# AS3364_waveform_VCA_0402_DIL_w_two_separ.net
KiCad netlist of a schematic drawn in EAGLE
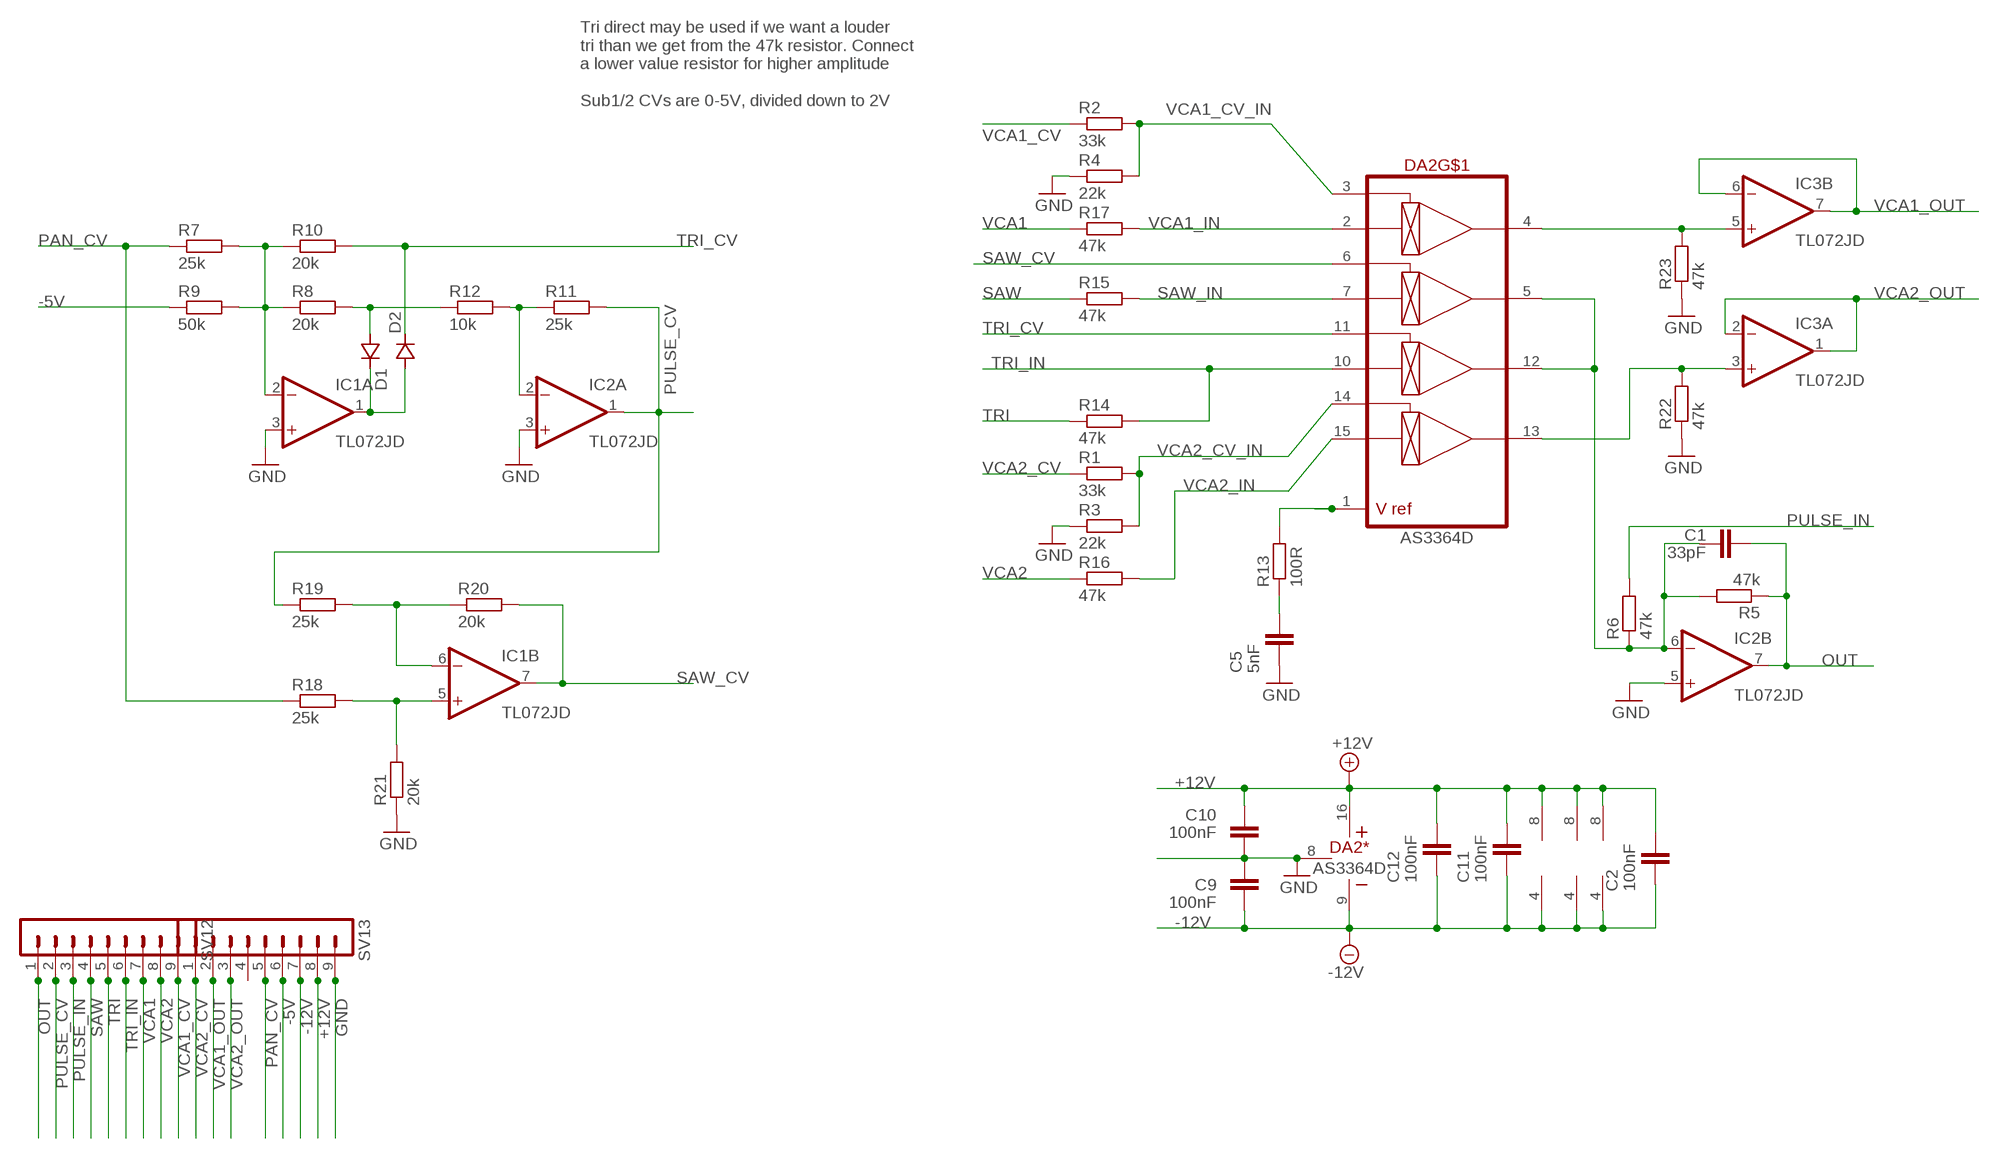
[diagram p0: schematic, sheet 1]

(export (version "E")
  (design (tool "Eeschema 10.0.6"))
  (components
    (comp (ref "C1")
      (value "33pF")
      (footprint "eagle-import:C0402")
      (libsource (lib "eagle-import") (part "C-EUC0402"))
    )
    (comp (ref "C2")
      (value "100nF")
      (footprint "eagle-import:C0402")
      (libsource (lib "eagle-import") (part "C-EUC0402"))
    )
    (comp (ref "C5")
      (value "5nF")
      (footprint "eagle-import:C0402")
      (libsource (lib "eagle-import") (part "C-EUC0402"))
    )
    (comp (ref "C9")
      (value "100nF")
      (footprint "eagle-import:C0402")
      (libsource (lib "eagle-import") (part "C-EUC0402"))
    )
    (comp (ref "C10")
      (value "100nF")
      (footprint "eagle-import:C0402")
      (libsource (lib "eagle-import") (part "C-EUC0402"))
    )
    (comp (ref "C11")
      (value "100nF")
      (footprint "eagle-import:C0402")
      (libsource (lib "eagle-import") (part "C-EUC0402"))
    )
    (comp (ref "C12")
      (value "100nF")
      (footprint "eagle-import:C0402")
      (libsource (lib "eagle-import") (part "C-EUC0402"))
    )
    (comp (ref "D1")
      (value "DIODESOD323")
      (footprint "eagle-import:SOD323J")
      (fields (field (name "MPN") "CDSOD323-T05C"))
      (libsource (lib "eagle-import") (part "DIODESOD323"))
    )
    (comp (ref "D2")
      (value "DIODESOD323")
      (footprint "eagle-import:SOD323J")
      (fields (field (name "MPN") "CDSOD323-T05C"))
      (libsource (lib "eagle-import") (part "DIODESOD323"))
    )
    (comp (ref "DA2")
      (value "AS3364D")
      (footprint "eagle-import:DIL16J")
      (libsource (lib "eagle-import") (part "AS3364D"))
    )
    (comp (ref "IC1")
      (value "TL072JD")
      (footprint "eagle-import:SO08J")
      (libsource (lib "eagle-import") (part "TL072JD"))
    )
    (comp (ref "IC2")
      (value "TL072JD")
      (footprint "eagle-import:SO08J")
      (libsource (lib "eagle-import") (part "TL072JD"))
    )
    (comp (ref "IC3")
      (value "TL072JD")
      (footprint "eagle-import:SO08J")
      (libsource (lib "eagle-import") (part "TL072JD"))
    )
    (comp (ref "R1")
      (value "33k")
      (footprint "eagle-import:R0402")
      (libsource (lib "eagle-import") (part "R-EU_R0402"))
    )
    (comp (ref "R2")
      (value "33k")
      (footprint "eagle-import:R0402")
      (libsource (lib "eagle-import") (part "R-EU_R0402"))
    )
    (comp (ref "R3")
      (value "22k")
      (footprint "eagle-import:R0402")
      (libsource (lib "eagle-import") (part "R-EU_R0402"))
    )
    (comp (ref "R4")
      (value "22k")
      (footprint "eagle-import:R0402")
      (libsource (lib "eagle-import") (part "R-EU_R0402"))
    )
    (comp (ref "R5")
      (value "47k")
      (footprint "eagle-import:R0402")
      (libsource (lib "eagle-import") (part "R-EU_R0402"))
    )
    (comp (ref "R6")
      (value "47k")
      (footprint "eagle-import:R0402")
      (libsource (lib "eagle-import") (part "R-EU_R0402"))
    )
    (comp (ref "R7")
      (value "25k")
      (footprint "eagle-import:R0402")
      (libsource (lib "eagle-import") (part "R-EU_R0402"))
    )
    (comp (ref "R8")
      (value "20k")
      (footprint "eagle-import:R0402")
      (libsource (lib "eagle-import") (part "R-EU_R0402"))
    )
    (comp (ref "R9")
      (value "50k")
      (footprint "eagle-import:R0402")
      (libsource (lib "eagle-import") (part "R-EU_R0402"))
    )
    (comp (ref "R10")
      (value "20k")
      (footprint "eagle-import:R0402")
      (libsource (lib "eagle-import") (part "R-EU_R0402"))
    )
    (comp (ref "R11")
      (value "25k")
      (footprint "eagle-import:R0402")
      (libsource (lib "eagle-import") (part "R-EU_R0402"))
    )
    (comp (ref "R12")
      (value "10k")
      (footprint "eagle-import:R0402")
      (libsource (lib "eagle-import") (part "R-EU_R0402"))
    )
    (comp (ref "R13")
      (value "100R")
      (footprint "eagle-import:R0402")
      (libsource (lib "eagle-import") (part "R-EU_R0402"))
    )
    (comp (ref "R14")
      (value "47k")
      (footprint "eagle-import:R0402")
      (libsource (lib "eagle-import") (part "R-EU_R0402"))
    )
    (comp (ref "R15")
      (value "47k")
      (footprint "eagle-import:R0402")
      (libsource (lib "eagle-import") (part "R-EU_R0402"))
    )
    (comp (ref "R16")
      (value "47k")
      (footprint "eagle-import:R0402")
      (libsource (lib "eagle-import") (part "R-EU_R0402"))
    )
    (comp (ref "R17")
      (value "47k")
      (footprint "eagle-import:R0402")
      (libsource (lib "eagle-import") (part "R-EU_R0402"))
    )
    (comp (ref "R18")
      (value "25k")
      (footprint "eagle-import:R0402")
      (libsource (lib "eagle-import") (part "R-EU_R0402"))
    )
    (comp (ref "R19")
      (value "25k")
      (footprint "eagle-import:R0402")
      (libsource (lib "eagle-import") (part "R-EU_R0402"))
    )
    (comp (ref "R20")
      (value "20k")
      (footprint "eagle-import:R0402")
      (libsource (lib "eagle-import") (part "R-EU_R0402"))
    )
    (comp (ref "R21")
      (value "20k")
      (footprint "eagle-import:R0402")
      (libsource (lib "eagle-import") (part "R-EU_R0402"))
    )
    (comp (ref "R22")
      (value "47k")
      (footprint "eagle-import:R0402")
      (libsource (lib "eagle-import") (part "R-EU_R0402"))
    )
    (comp (ref "R23")
      (value "47k")
      (footprint "eagle-import:R0402")
      (libsource (lib "eagle-import") (part "R-EU_R0402"))
    )
    (comp (ref "SV12")
      (value "MA09-1JP")
      (footprint "eagle-import:SIP-PIN09-1J")
      (libsource (lib "eagle-import") (part "MA09-1JP"))
    )
    (comp (ref "SV13")
      (value "MA09-1JP")
      (footprint "eagle-import:SIP-PIN09-1J")
      (libsource (lib "eagle-import") (part "MA09-1JP"))
    )
  )
  (nets
    (net (code "1") (name "+12V") (class "Default")
      (node (ref "C10") (pin "2") (pinfunction "2_2") (pintype "passive"))
      (node (ref "C11") (pin "2") (pinfunction "2_2") (pintype "passive"))
      (node (ref "C12") (pin "2") (pinfunction "2_2") (pintype "passive"))
      (node (ref "C2") (pin "2") (pinfunction "2_2") (pintype "passive"))
      (node (ref "DA2") (pin "16") (pinfunction "V+_16") (pintype "power_in"))
      (node (ref "IC1") (pin "8") (pinfunction "V+_8") (pintype "power_in"))
      (node (ref "IC2") (pin "8") (pinfunction "V+_8") (pintype "power_in"))
      (node (ref "IC3") (pin "8") (pinfunction "V+_8") (pintype "power_in"))
      (node (ref "SV13") (pin "8") (pinfunction "8_8") (pintype "passive"))
    )
    (net (code "2") (name "-12V") (class "Default")
      (node (ref "C11") (pin "1") (pinfunction "1_1") (pintype "passive"))
      (node (ref "C12") (pin "1") (pinfunction "1_1") (pintype "passive"))
      (node (ref "C2") (pin "1") (pinfunction "1_1") (pintype "passive"))
      (node (ref "C9") (pin "1") (pinfunction "1_1") (pintype "passive"))
      (node (ref "DA2") (pin "9") (pinfunction "V-_9") (pintype "power_in"))
      (node (ref "IC1") (pin "4") (pinfunction "V-_4") (pintype "power_in"))
      (node (ref "IC2") (pin "4") (pinfunction "V-_4") (pintype "power_in"))
      (node (ref "IC3") (pin "4") (pinfunction "V-_4") (pintype "power_in"))
      (node (ref "SV13") (pin "7") (pinfunction "7_7") (pintype "passive"))
    )
    (net (code "3") (name "/-5V") (class "Default")
      (node (ref "R9") (pin "1") (pinfunction "1_1") (pintype "passive"))
      (node (ref "SV13") (pin "6") (pinfunction "6_6") (pintype "passive"))
    )
    (net (code "4") (name "/OUT") (class "Default")
      (node (ref "C1") (pin "1") (pinfunction "1_1") (pintype "passive"))
      (node (ref "IC2") (pin "7") (pinfunction "OUT_7") (pintype "output"))
      (node (ref "R5") (pin "1") (pinfunction "1_1") (pintype "passive"))
      (node (ref "SV12") (pin "1") (pinfunction "1_1") (pintype "passive"))
    )
    (net (code "5") (name "/PAN_CV") (class "Default")
      (node (ref "R18") (pin "1") (pinfunction "1_1") (pintype "passive"))
      (node (ref "R7") (pin "1") (pinfunction "1_1") (pintype "passive"))
      (node (ref "SV13") (pin "5") (pinfunction "5_5") (pintype "passive"))
    )
    (net (code "6") (name "/PULSE_CV") (class "Default")
      (node (ref "IC2") (pin "1") (pinfunction "OUT_1") (pintype "output"))
      (node (ref "R11") (pin "2") (pinfunction "2_2") (pintype "passive"))
      (node (ref "R19") (pin "1") (pinfunction "1_1") (pintype "passive"))
      (node (ref "SV12") (pin "2") (pinfunction "2_2") (pintype "passive"))
    )
    (net (code "7") (name "/PULSE_IN") (class "Default")
      (node (ref "R6") (pin "2") (pinfunction "2_2") (pintype "passive"))
      (node (ref "SV12") (pin "3") (pinfunction "3_3") (pintype "passive"))
    )
    (net (code "8") (name "/SAW") (class "Default")
      (node (ref "R15") (pin "1") (pinfunction "1_1") (pintype "passive"))
      (node (ref "SV12") (pin "4") (pinfunction "4_4") (pintype "passive"))
    )
    (net (code "9") (name "/SAW_CV") (class "Default")
      (node (ref "DA2") (pin "6") (pinfunction "CV2_6") (pintype "input"))
      (node (ref "IC1") (pin "7") (pinfunction "OUT_7") (pintype "output"))
      (node (ref "R20") (pin "2") (pinfunction "2_2") (pintype "passive"))
    )
    (net (code "10") (name "/SAW_IN") (class "Default")
      (node (ref "DA2") (pin "7") (pinfunction "IN2_7") (pintype "input"))
      (node (ref "R15") (pin "2") (pinfunction "2_2") (pintype "passive"))
    )
    (net (code "11") (name "/TRI") (class "Default")
      (node (ref "R14") (pin "1") (pinfunction "1_1") (pintype "passive"))
      (node (ref "SV12") (pin "5") (pinfunction "5_5") (pintype "passive"))
    )
    (net (code "12") (name "/TRI_CV") (class "Default")
      (node (ref "D2") (pin "1") (pinfunction "C_1") (pintype "passive"))
      (node (ref "DA2") (pin "11") (pinfunction "CV3_11") (pintype "input"))
      (node (ref "R10") (pin "2") (pinfunction "2_2") (pintype "passive"))
    )
    (net (code "13") (name "/TRI_IN") (class "Default")
      (node (ref "DA2") (pin "10") (pinfunction "IN3_10") (pintype "input"))
      (node (ref "R14") (pin "2") (pinfunction "2_2") (pintype "passive"))
      (node (ref "SV12") (pin "6") (pinfunction "6_6") (pintype "passive"))
    )
    (net (code "14") (name "/VCA1") (class "Default")
      (node (ref "R17") (pin "1") (pinfunction "1_1") (pintype "passive"))
      (node (ref "SV12") (pin "7") (pinfunction "7_7") (pintype "passive"))
    )
    (net (code "15") (name "/VCA1_CV") (class "Default")
      (node (ref "R2") (pin "1") (pinfunction "1_1") (pintype "passive"))
      (node (ref "SV12") (pin "9") (pinfunction "9_9") (pintype "passive"))
    )
    (net (code "16") (name "/VCA1_CV_IN") (class "Default")
      (node (ref "DA2") (pin "3") (pinfunction "CV1_3") (pintype "input"))
      (node (ref "R2") (pin "2") (pinfunction "2_2") (pintype "passive"))
      (node (ref "R4") (pin "2") (pinfunction "2_2") (pintype "passive"))
    )
    (net (code "17") (name "/VCA1_IN") (class "Default")
      (node (ref "DA2") (pin "2") (pinfunction "IN1_2") (pintype "input"))
      (node (ref "R17") (pin "2") (pinfunction "2_2") (pintype "passive"))
    )
    (net (code "18") (name "/VCA1_OUT") (class "Default")
      (node (ref "IC3") (pin "6") (pinfunction "-IN_6") (pintype "input"))
      (node (ref "IC3") (pin "7") (pinfunction "OUT_7") (pintype "output"))
      (node (ref "SV13") (pin "2") (pinfunction "2_2") (pintype "passive"))
    )
    (net (code "19") (name "/VCA2") (class "Default")
      (node (ref "R16") (pin "1") (pinfunction "1_1") (pintype "passive"))
      (node (ref "SV12") (pin "8") (pinfunction "8_8") (pintype "passive"))
    )
    (net (code "20") (name "/VCA2_CV") (class "Default")
      (node (ref "R1") (pin "1") (pinfunction "1_1") (pintype "passive"))
      (node (ref "SV13") (pin "1") (pinfunction "1_1") (pintype "passive"))
    )
    (net (code "21") (name "/VCA2_CV_IN") (class "Default")
      (node (ref "DA2") (pin "14") (pinfunction "CV4_14") (pintype "input"))
      (node (ref "R1") (pin "2") (pinfunction "2_2") (pintype "passive"))
      (node (ref "R3") (pin "2") (pinfunction "2_2") (pintype "passive"))
    )
    (net (code "22") (name "/VCA2_IN") (class "Default")
      (node (ref "DA2") (pin "15") (pinfunction "IN4_15") (pintype "input"))
      (node (ref "R16") (pin "2") (pinfunction "2_2") (pintype "passive"))
    )
    (net (code "23") (name "/VCA2_OUT") (class "Default")
      (node (ref "IC3") (pin "1") (pinfunction "OUT_1") (pintype "output"))
      (node (ref "IC3") (pin "2") (pinfunction "-IN_2") (pintype "input"))
      (node (ref "SV13") (pin "3") (pinfunction "3_3") (pintype "passive"))
    )
    (net (code "24") (name "GND") (class "Default")
      (node (ref "C10") (pin "1") (pinfunction "1_1") (pintype "passive"))
      (node (ref "C5") (pin "1") (pinfunction "1_1") (pintype "passive"))
      (node (ref "C9") (pin "2") (pinfunction "2_2") (pintype "passive"))
      (node (ref "DA2") (pin "8") (pinfunction "GND_8") (pintype "power_in"))
      (node (ref "IC1") (pin "3") (pinfunction "+IN_3") (pintype "input"))
      (node (ref "IC2") (pin "3") (pinfunction "+IN_3") (pintype "input"))
      (node (ref "IC2") (pin "5") (pinfunction "+IN_5") (pintype "input"))
      (node (ref "R21") (pin "1") (pinfunction "1_1") (pintype "passive"))
      (node (ref "R22") (pin "1") (pinfunction "1_1") (pintype "passive"))
      (node (ref "R23") (pin "1") (pinfunction "1_1") (pintype "passive"))
      (node (ref "R3") (pin "1") (pinfunction "1_1") (pintype "passive"))
      (node (ref "R4") (pin "1") (pinfunction "1_1") (pintype "passive"))
      (node (ref "SV13") (pin "9") (pinfunction "9_9") (pintype "passive"))
    )
    (net (code "25") (name "Net-(C5-Pad2)") (class "Default")
      (node (ref "C5") (pin "2") (pinfunction "2_2") (pintype "passive"))
      (node (ref "R13") (pin "1") (pinfunction "1_1") (pintype "passive"))
    )
    (net (code "26") (name "Net-(D1-A)") (class "Default")
      (node (ref "D1") (pin "2") (pinfunction "A_2") (pintype "passive"))
      (node (ref "R12") (pin "1") (pinfunction "1_1") (pintype "passive"))
      (node (ref "R8") (pin "2") (pinfunction "2_2") (pintype "passive"))
    )
    (net (code "27") (name "Net-(D1-C)") (class "Default")
      (node (ref "D1") (pin "1") (pinfunction "C_1") (pintype "passive"))
      (node (ref "D2") (pin "2") (pinfunction "A_2") (pintype "passive"))
      (node (ref "IC1") (pin "1") (pinfunction "OUT_1") (pintype "output"))
    )
    (net (code "28") (name "Net-(DA2B-OUT1)") (class "Default")
      (node (ref "DA2") (pin "4") (pinfunction "OUT1_4") (pintype "output"))
      (node (ref "IC3") (pin "5") (pinfunction "+IN_5") (pintype "input"))
      (node (ref "R23") (pin "2") (pinfunction "2_2") (pintype "passive"))
    )
    (net (code "29") (name "Net-(DA2B-OUT2)") (class "Default")
      (node (ref "C1") (pin "2") (pinfunction "2_2") (pintype "passive"))
      (node (ref "DA2") (pin "12") (pinfunction "OUT3_12") (pintype "output"))
      (node (ref "DA2") (pin "5") (pinfunction "OUT2_5") (pintype "output"))
      (node (ref "IC2") (pin "6") (pinfunction "-IN_6") (pintype "input"))
      (node (ref "R5") (pin "2") (pinfunction "2_2") (pintype "passive"))
      (node (ref "R6") (pin "1") (pinfunction "1_1") (pintype "passive"))
    )
    (net (code "30") (name "Net-(DA2B-OUT4)") (class "Default")
      (node (ref "DA2") (pin "13") (pinfunction "OUT4_13") (pintype "output"))
      (node (ref "IC3") (pin "3") (pinfunction "+IN_3") (pintype "input"))
      (node (ref "R22") (pin "2") (pinfunction "2_2") (pintype "passive"))
    )
    (net (code "31") (name "Net-(DA2B-VREF)") (class "Default")
      (node (ref "DA2") (pin "1") (pinfunction "VREF_1") (pintype "output"))
      (node (ref "R13") (pin "2") (pinfunction "2_2") (pintype "passive"))
    )
    (net (code "32") (name "Net-(IC1A--IN)") (class "Default")
      (node (ref "IC1") (pin "2") (pinfunction "-IN_2") (pintype "input"))
      (node (ref "R10") (pin "1") (pinfunction "1_1") (pintype "passive"))
      (node (ref "R7") (pin "2") (pinfunction "2_2") (pintype "passive"))
      (node (ref "R8") (pin "1") (pinfunction "1_1") (pintype "passive"))
      (node (ref "R9") (pin "2") (pinfunction "2_2") (pintype "passive"))
    )
    (net (code "33") (name "Net-(IC1B-+IN)") (class "Default")
      (node (ref "IC1") (pin "5") (pinfunction "+IN_5") (pintype "input"))
      (node (ref "R18") (pin "2") (pinfunction "2_2") (pintype "passive"))
      (node (ref "R21") (pin "2") (pinfunction "2_2") (pintype "passive"))
    )
    (net (code "34") (name "Net-(IC1B--IN)") (class "Default")
      (node (ref "IC1") (pin "6") (pinfunction "-IN_6") (pintype "input"))
      (node (ref "R19") (pin "2") (pinfunction "2_2") (pintype "passive"))
      (node (ref "R20") (pin "1") (pinfunction "1_1") (pintype "passive"))
    )
    (net (code "35") (name "Net-(IC2A--IN)") (class "Default")
      (node (ref "IC2") (pin "2") (pinfunction "-IN_2") (pintype "input"))
      (node (ref "R11") (pin "1") (pinfunction "1_1") (pintype "passive"))
      (node (ref "R12") (pin "2") (pinfunction "2_2") (pintype "passive"))
    )
    (net (code "36") (name "unconnected-(SV13-Pad4)") (class "Default")
      (node (ref "SV13") (pin "4") (pinfunction "4_4") (pintype "passive"))
    )
  )
)
